# display.net
KiCad netlist of a schematic drawn in EAGLE
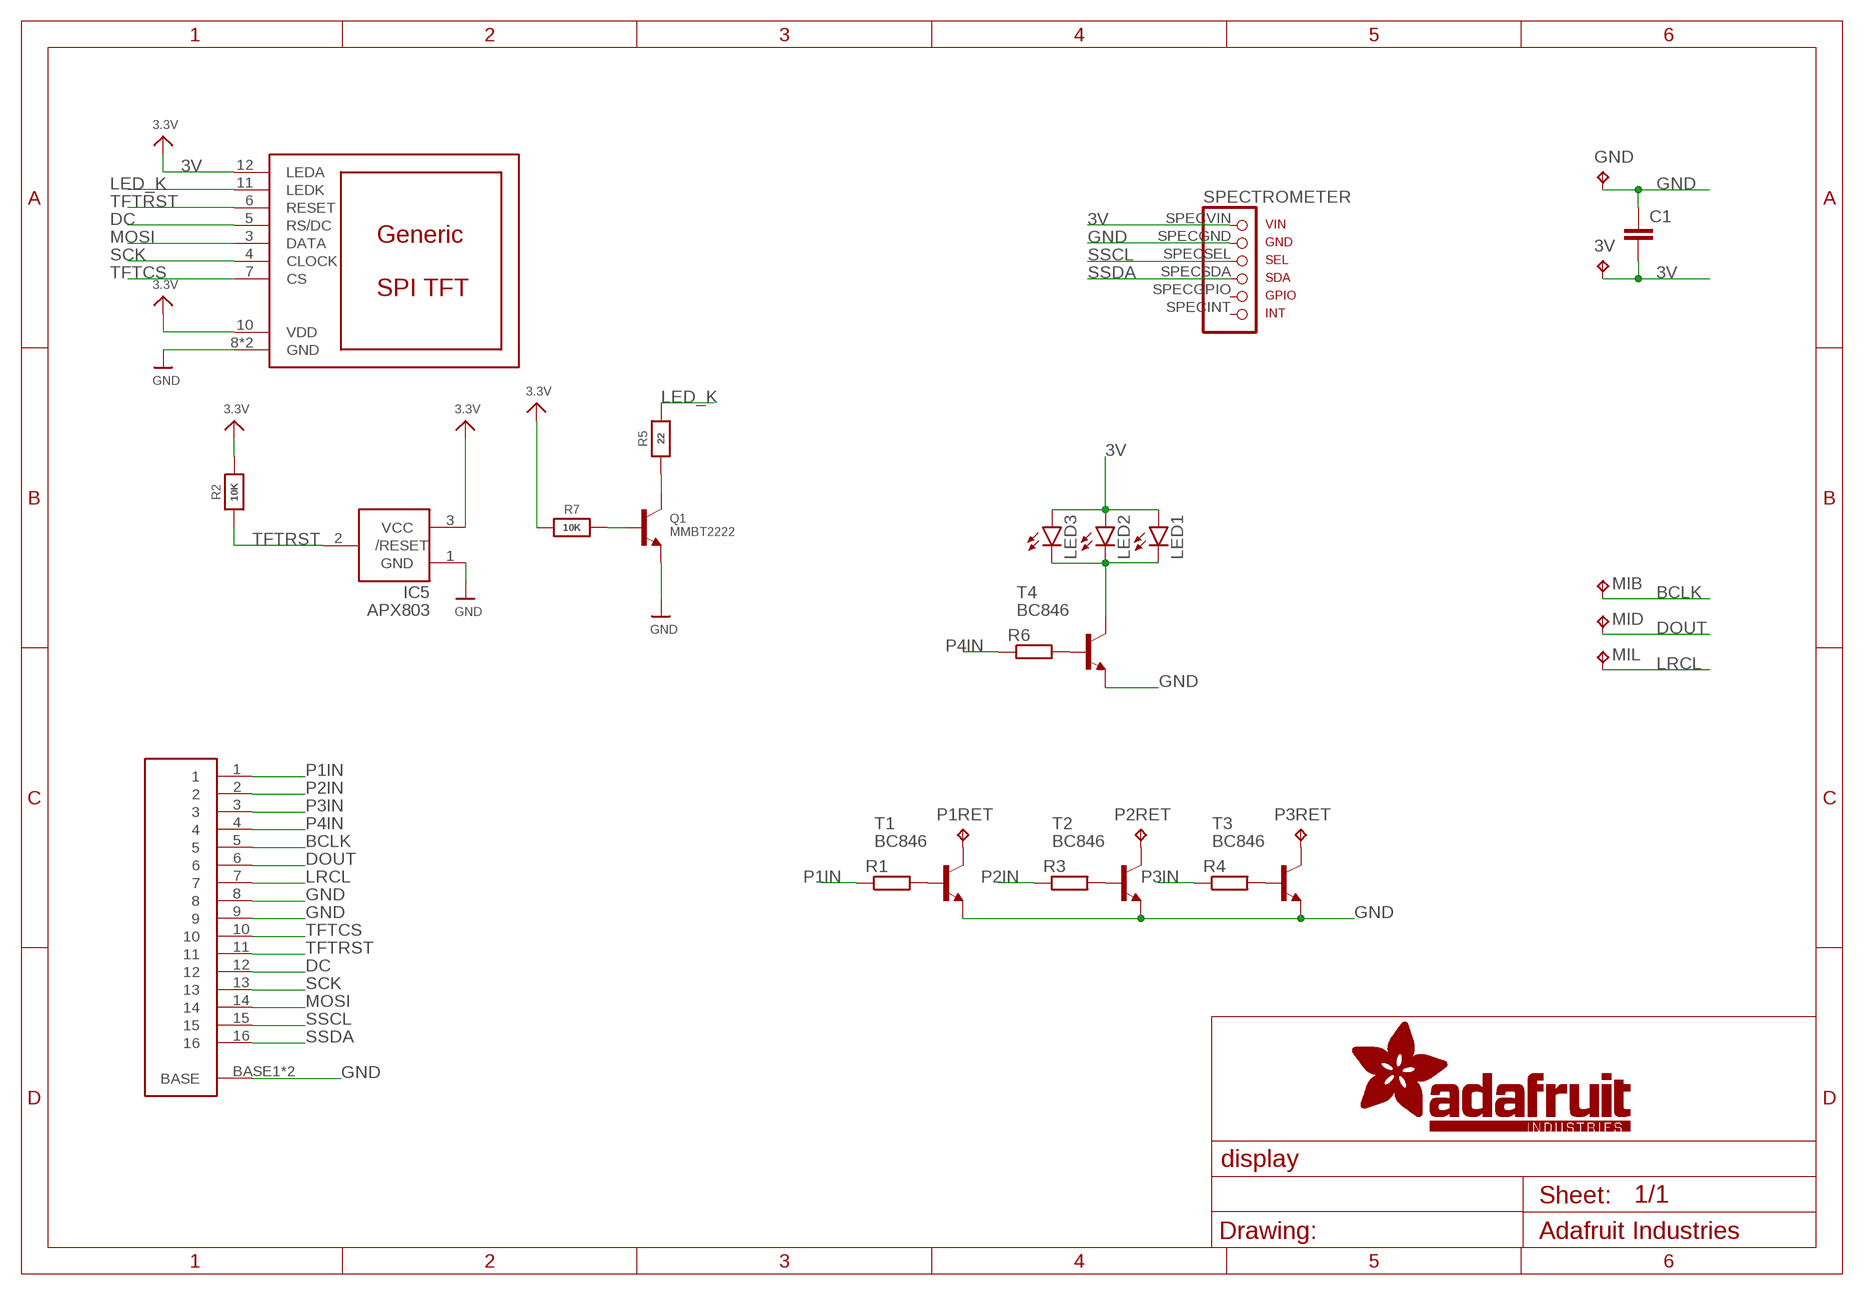
[diagram p0: schematic, sheet 1]

(export (version "E")
  (design (tool "Eeschema 10.0.6"))
  (components
    (comp (ref "3V")
      (value "TPTP20R")
      (footprint "eagle-import:TP20R")
      (libsource (lib "eagle-import") (part "TPTP20R"))
    )
    (comp (ref "C1")
      (value "C-EUC0805")
      (footprint "eagle-import:C0805")
      (libsource (lib "eagle-import") (part "C-EUC0805"))
    )
    (comp (ref "DISP1")
      (value "DISP_LCD_GENERIC_SPI_1.14IN_240X135_WRAPUNDER")
      (footprint "eagle-import:TFT_1.14IN_240X135_WRAPUNDER")
      (libsource (lib "eagle-import") (part "DISP_LCD_GENERIC_SPI_1.14IN_240X135_WRAPUNDER"))
    )
    (comp (ref "GND")
      (value "TPTP20R")
      (footprint "eagle-import:TP20R")
      (libsource (lib "eagle-import") (part "TPTP20R"))
    )
    (comp (ref "IC5")
      (value "APX803")
      (footprint "eagle-import:SOT23")
      (libsource (lib "eagle-import") (part "AXP083-SAG"))
    )
    (comp (ref "LED1")
      (value "LED3MM")
      (footprint "eagle-import:LED3MM")
      (libsource (lib "eagle-import") (part "LED3MM"))
    )
    (comp (ref "LED2")
      (value "LED3MM")
      (footprint "eagle-import:LED3MM")
      (libsource (lib "eagle-import") (part "LED3MM"))
    )
    (comp (ref "LED3")
      (value "LED3MM")
      (footprint "eagle-import:LED3MM")
      (libsource (lib "eagle-import") (part "LED3MM"))
    )
    (comp (ref "MIB")
      (value "TPTP10R")
      (footprint "eagle-import:TP10R")
      (libsource (lib "eagle-import") (part "TPTP10R"))
    )
    (comp (ref "MID")
      (value "TPTP10R")
      (footprint "eagle-import:TP10R")
      (libsource (lib "eagle-import") (part "TPTP10R"))
    )
    (comp (ref "MIL")
      (value "TPTP10R")
      (footprint "eagle-import:TP10R")
      (libsource (lib "eagle-import") (part "TPTP10R"))
    )
    (comp (ref "P1RET")
      (value "TPTP10R")
      (footprint "eagle-import:TP10R")
      (libsource (lib "eagle-import") (part "TPTP10R"))
    )
    (comp (ref "P2RET")
      (value "TPTP10R")
      (footprint "eagle-import:TP10R")
      (libsource (lib "eagle-import") (part "TPTP10R"))
    )
    (comp (ref "P3RET")
      (value "TPTP10R")
      (footprint "eagle-import:TP10R")
      (libsource (lib "eagle-import") (part "TPTP10R"))
    )
    (comp (ref "Q1")
      (value "MMBT2222")
      (footprint "eagle-import:SOT23-WIDE")
      (libsource (lib "eagle-import") (part "TRANSISTOR_NPNWIDE"))
    )
    (comp (ref "R1")
      (value "R-EU_R0805")
      (footprint "eagle-import:R0805")
      (libsource (lib "eagle-import") (part "R-EU_R0805"))
    )
    (comp (ref "R2")
      (value "10K")
      (footprint "eagle-import:0603-NO")
      (libsource (lib "eagle-import") (part "RESISTOR_0603_NOOUT"))
    )
    (comp (ref "R3")
      (value "R-EU_R0805")
      (footprint "eagle-import:R0805")
      (libsource (lib "eagle-import") (part "R-EU_R0805"))
    )
    (comp (ref "R4")
      (value "R-EU_R0805")
      (footprint "eagle-import:R0805")
      (libsource (lib "eagle-import") (part "R-EU_R0805"))
    )
    (comp (ref "R5")
      (value "22")
      (footprint "eagle-import:0603-NO")
      (libsource (lib "eagle-import") (part "RESISTOR_0603_NOOUT"))
    )
    (comp (ref "R6")
      (value "R-EU_R0805")
      (footprint "eagle-import:R0805")
      (libsource (lib "eagle-import") (part "R-EU_R0805"))
    )
    (comp (ref "R7")
      (value "10K")
      (footprint "eagle-import:0603-NO")
      (libsource (lib "eagle-import") (part "RESISTOR_0603_NOOUT"))
    )
    (comp (ref "T1")
      (value "BC846")
      (footprint "eagle-import:SOT23")
      (libsource (lib "eagle-import") (part "BC846"))
    )
    (comp (ref "T2")
      (value "BC846")
      (footprint "eagle-import:SOT23")
      (libsource (lib "eagle-import") (part "BC846"))
    )
    (comp (ref "T3")
      (value "BC846")
      (footprint "eagle-import:SOT23")
      (libsource (lib "eagle-import") (part "BC846"))
    )
    (comp (ref "T4")
      (value "BC846")
      (footprint "eagle-import:SOT23")
      (libsource (lib "eagle-import") (part "BC846"))
    )
    (comp (ref "U$2")
      (value "SPECTROMETER")
      (footprint "eagle-import:SPECTROMETER")
      (libsource (lib "eagle-import") (part "SPECTROMETER"))
    )
    (comp (ref "U$3")
      (value "16PINFFC")
      (footprint "eagle-import:16PINFFC")
      (libsource (lib "eagle-import") (part "16PINFFC"))
    )
  )
  (nets
    (net (code "1") (name "/BCLK") (class "Default")
      (node (ref "MIB") (pin "TP") (pinfunction "TP_TP") (pintype "input"))
      (node (ref "U$3") (pin "5") (pinfunction "5_5") (pintype "bidirectional"))
    )
    (net (code "2") (name "/DC") (class "Default")
      (node (ref "DISP1") (pin "5") (pinfunction "RS/DC_5") (pintype "input"))
      (node (ref "U$3") (pin "12") (pinfunction "12_12") (pintype "bidirectional"))
    )
    (net (code "3") (name "/DOUT") (class "Default")
      (node (ref "MID") (pin "TP") (pinfunction "TP_TP") (pintype "input"))
      (node (ref "U$3") (pin "6") (pinfunction "6_6") (pintype "bidirectional"))
    )
    (net (code "4") (name "/LED_K") (class "Default")
      (node (ref "DISP1") (pin "11") (pinfunction "LEDK_11") (pintype "input"))
      (node (ref "R5") (pin "2") (pinfunction "2_2") (pintype "passive"))
    )
    (net (code "5") (name "/LRCL") (class "Default")
      (node (ref "MIL") (pin "TP") (pinfunction "TP_TP") (pintype "input"))
      (node (ref "U$3") (pin "7") (pinfunction "7_7") (pintype "bidirectional"))
    )
    (net (code "6") (name "/MOSI") (class "Default")
      (node (ref "DISP1") (pin "3") (pinfunction "DATA_3") (pintype "bidirectional"))
      (node (ref "U$3") (pin "14") (pinfunction "14_14") (pintype "bidirectional"))
    )
    (net (code "7") (name "/P1IN") (class "Default")
      (node (ref "R1") (pin "1") (pinfunction "1_1") (pintype "passive"))
      (node (ref "U$3") (pin "1") (pinfunction "1_1") (pintype "bidirectional"))
    )
    (net (code "8") (name "/P2IN") (class "Default")
      (node (ref "R3") (pin "1") (pinfunction "1_1") (pintype "passive"))
      (node (ref "U$3") (pin "2") (pinfunction "2_2") (pintype "bidirectional"))
    )
    (net (code "9") (name "/P3IN") (class "Default")
      (node (ref "R4") (pin "1") (pinfunction "1_1") (pintype "passive"))
      (node (ref "U$3") (pin "3") (pinfunction "3_3") (pintype "bidirectional"))
    )
    (net (code "10") (name "/P4IN") (class "Default")
      (node (ref "R6") (pin "1") (pinfunction "1_1") (pintype "passive"))
      (node (ref "U$3") (pin "4") (pinfunction "4_4") (pintype "bidirectional"))
    )
    (net (code "11") (name "/SCK") (class "Default")
      (node (ref "DISP1") (pin "4") (pinfunction "CLOCK_4") (pintype "input"))
      (node (ref "U$3") (pin "13") (pinfunction "13_13") (pintype "bidirectional"))
    )
    (net (code "12") (name "/SSCL") (class "Default")
      (node (ref "U$2") (pin "SPECSEL") (pinfunction "SPECSEL_SPECSEL") (pintype "passive"))
      (node (ref "U$3") (pin "15") (pinfunction "15_15") (pintype "bidirectional"))
    )
    (net (code "13") (name "/SSDA") (class "Default")
      (node (ref "U$2") (pin "SPECSDA") (pinfunction "SPECSDA_SPECSDA") (pintype "passive"))
      (node (ref "U$3") (pin "16") (pinfunction "16_16") (pintype "bidirectional"))
    )
    (net (code "14") (name "/TFTCS") (class "Default")
      (node (ref "DISP1") (pin "7") (pinfunction "CS_7") (pintype "input"))
      (node (ref "U$3") (pin "10") (pinfunction "10_10") (pintype "bidirectional"))
    )
    (net (code "15") (name "/TFTRST") (class "Default")
      (node (ref "DISP1") (pin "6") (pinfunction "RESET_6") (pintype "input"))
      (node (ref "IC5") (pin "2") (pinfunction "/RESET_2") (pintype "output"))
      (node (ref "R2") (pin "1") (pinfunction "1_1") (pintype "passive"))
      (node (ref "U$3") (pin "11") (pinfunction "11_11") (pintype "bidirectional"))
    )
    (net (code "16") (name "3.3V") (class "Default")
      (node (ref "3V") (pin "TP") (pinfunction "TP_TP") (pintype "input"))
      (node (ref "C1") (pin "2") (pinfunction "2_2") (pintype "passive"))
      (node (ref "DISP1") (pin "10") (pinfunction "VDD_10") (pintype "power_in"))
      (node (ref "DISP1") (pin "12") (pinfunction "LEDA_12") (pintype "input"))
      (node (ref "IC5") (pin "3") (pinfunction "VCC_3") (pintype "power_in"))
      (node (ref "LED1") (pin "A") (pinfunction "A_A") (pintype "passive"))
      (node (ref "LED2") (pin "A") (pinfunction "A_A") (pintype "passive"))
      (node (ref "LED3") (pin "A") (pinfunction "A_A") (pintype "passive"))
      (node (ref "R2") (pin "2") (pinfunction "2_2") (pintype "passive"))
      (node (ref "R7") (pin "1") (pinfunction "1_1") (pintype "passive"))
      (node (ref "U$2") (pin "SPECVIN") (pinfunction "SPECVIN_SPECVIN") (pintype "passive"))
    )
    (net (code "17") (name "GND") (class "Default")
      (node (ref "C1") (pin "1") (pinfunction "1_1") (pintype "passive"))
      (node (ref "DISP1") (pin "13") (pinfunction "GND_13") (pintype "power_in"))
      (node (ref "DISP1") (pin "8") (pinfunction "GND_8") (pintype "power_in"))
      (node (ref "GND") (pin "TP") (pinfunction "TP_TP") (pintype "input"))
      (node (ref "IC5") (pin "1") (pinfunction "GND_1") (pintype "power_in"))
      (node (ref "Q1") (pin "2") (pinfunction "E_2") (pintype "passive"))
      (node (ref "T1") (pin "2") (pinfunction "E_2") (pintype "passive"))
      (node (ref "T2") (pin "2") (pinfunction "E_2") (pintype "passive"))
      (node (ref "T3") (pin "2") (pinfunction "E_2") (pintype "passive"))
      (node (ref "T4") (pin "2") (pinfunction "E_2") (pintype "passive"))
      (node (ref "U$2") (pin "SPECGND") (pinfunction "SPECGND_SPECGND") (pintype "passive"))
      (node (ref "U$3") (pin "8") (pinfunction "8_8") (pintype "bidirectional"))
      (node (ref "U$3") (pin "9") (pinfunction "9_9") (pintype "bidirectional"))
      (node (ref "U$3") (pin "BASE1") (pinfunction "BASE_BASE1") (pintype "bidirectional"))
      (node (ref "U$3") (pin "BASE2") (pinfunction "BASE_BASE2") (pintype "bidirectional"))
    )
    (net (code "18") (name "Net-(LED1-C)") (class "Default")
      (node (ref "LED1") (pin "K") (pinfunction "C_K") (pintype "passive"))
      (node (ref "LED2") (pin "K") (pinfunction "C_K") (pintype "passive"))
      (node (ref "LED3") (pin "K") (pinfunction "C_K") (pintype "passive"))
      (node (ref "T4") (pin "3") (pinfunction "C_3") (pintype "passive"))
    )
    (net (code "19") (name "Net-(Q1-B)") (class "Default")
      (node (ref "Q1") (pin "1") (pinfunction "B_1") (pintype "passive"))
      (node (ref "R7") (pin "2") (pinfunction "2_2") (pintype "passive"))
    )
    (net (code "20") (name "Net-(Q1-C)") (class "Default")
      (node (ref "Q1") (pin "3") (pinfunction "C_3") (pintype "passive"))
      (node (ref "R5") (pin "1") (pinfunction "1_1") (pintype "passive"))
    )
    (net (code "21") (name "Net-(T1-B)") (class "Default")
      (node (ref "R1") (pin "2") (pinfunction "2_2") (pintype "passive"))
      (node (ref "T1") (pin "1") (pinfunction "B_1") (pintype "passive"))
    )
    (net (code "22") (name "Net-(T1-C)") (class "Default")
      (node (ref "P1RET") (pin "TP") (pinfunction "TP_TP") (pintype "input"))
      (node (ref "T1") (pin "3") (pinfunction "C_3") (pintype "passive"))
    )
    (net (code "23") (name "Net-(T2-B)") (class "Default")
      (node (ref "R3") (pin "2") (pinfunction "2_2") (pintype "passive"))
      (node (ref "T2") (pin "1") (pinfunction "B_1") (pintype "passive"))
    )
    (net (code "24") (name "Net-(T2-C)") (class "Default")
      (node (ref "P2RET") (pin "TP") (pinfunction "TP_TP") (pintype "input"))
      (node (ref "T2") (pin "3") (pinfunction "C_3") (pintype "passive"))
    )
    (net (code "25") (name "Net-(T3-B)") (class "Default")
      (node (ref "R4") (pin "2") (pinfunction "2_2") (pintype "passive"))
      (node (ref "T3") (pin "1") (pinfunction "B_1") (pintype "passive"))
    )
    (net (code "26") (name "Net-(T3-C)") (class "Default")
      (node (ref "P3RET") (pin "TP") (pinfunction "TP_TP") (pintype "input"))
      (node (ref "T3") (pin "3") (pinfunction "C_3") (pintype "passive"))
    )
    (net (code "27") (name "Net-(T4-B)") (class "Default")
      (node (ref "R6") (pin "2") (pinfunction "2_2") (pintype "passive"))
      (node (ref "T4") (pin "1") (pinfunction "B_1") (pintype "passive"))
    )
    (net (code "28") (name "unconnected-(U$2-PadSPECGPIO)") (class "Default")
      (node (ref "U$2") (pin "SPECGPIO") (pinfunction "SPECGPIO_SPECGPIO") (pintype "passive"))
    )
    (net (code "29") (name "unconnected-(U$2-PadSPECINT)") (class "Default")
      (node (ref "U$2") (pin "SPECINT") (pinfunction "SPECINT_SPECINT") (pintype "passive"))
    )
  )
)
